# kl26z.net
KiCad netlist of a schematic drawn in EAGLE
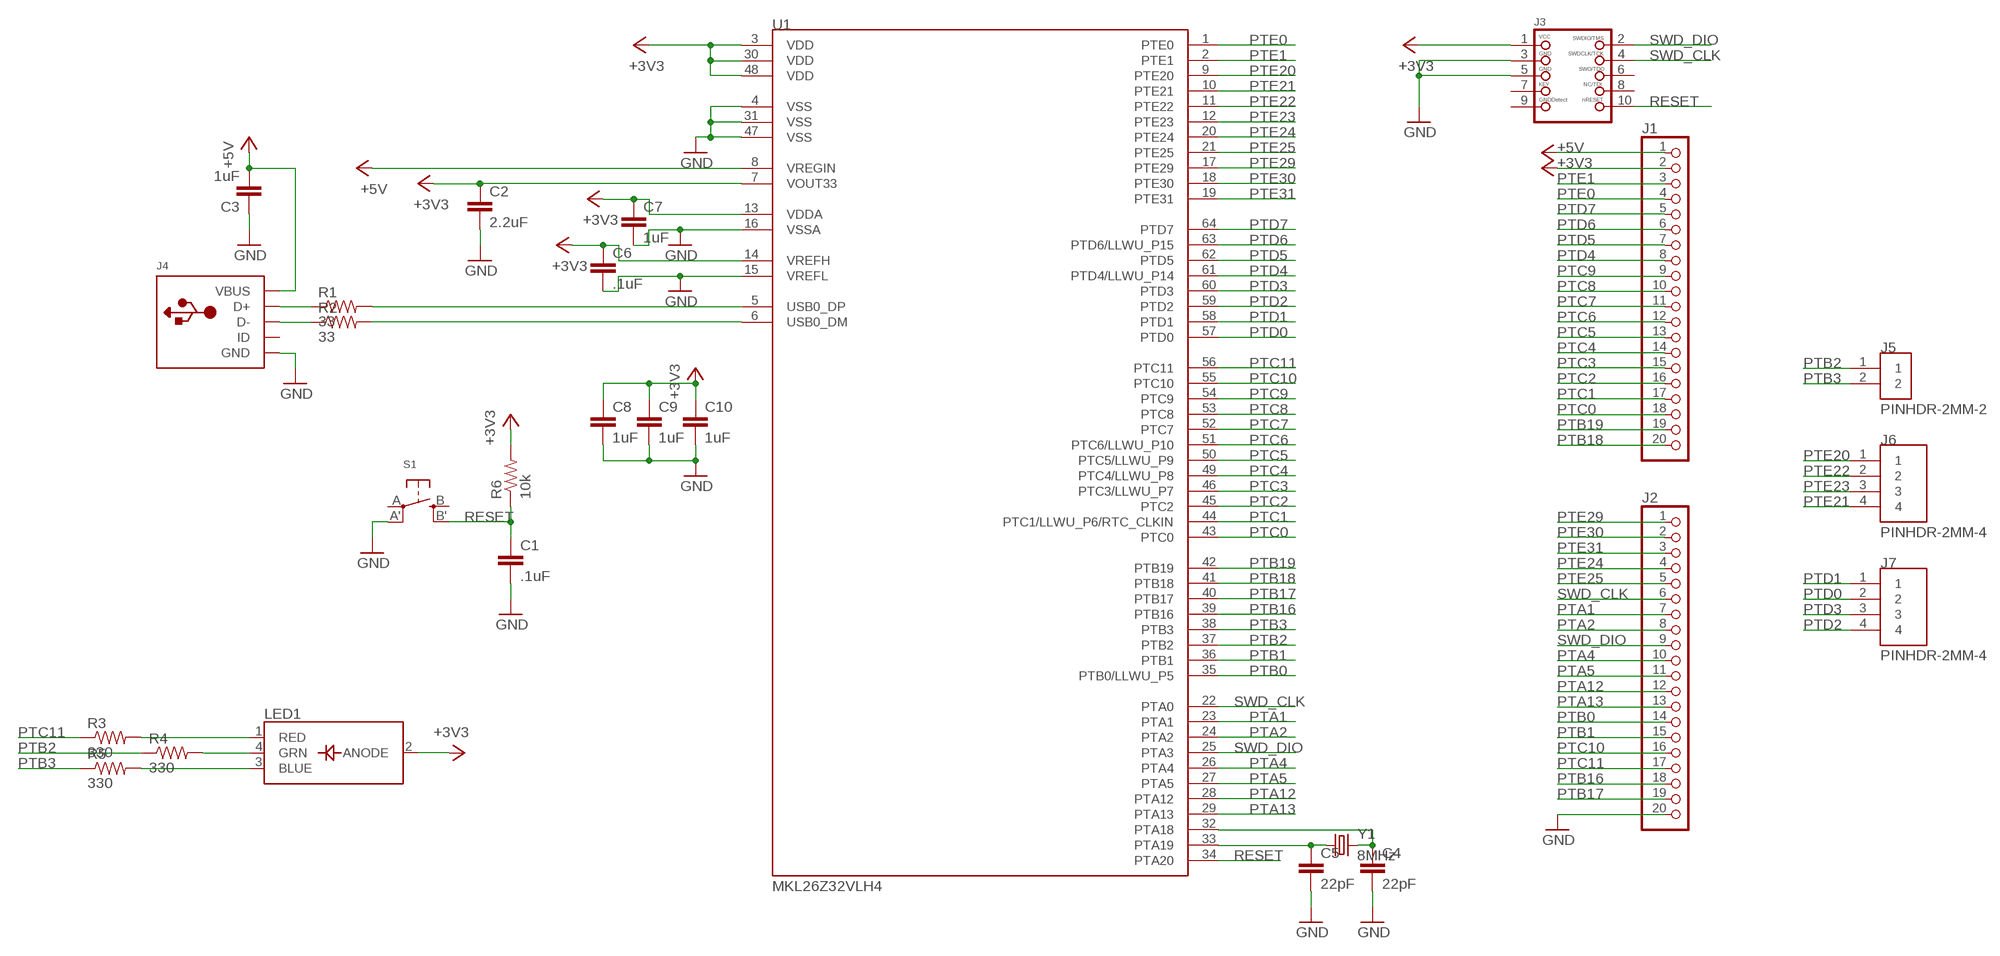
[diagram p0: schematic, sheet 1]

(export (version "E")
  (design (tool "Eeschema 10.0.6"))
  (components
    (comp (ref "C1")
      (value ".1uF")
      (footprint "eagle-import:C0603")
      (libsource (lib "eagle-import") (part "C-EUC0603"))
    )
    (comp (ref "C2")
      (value "2.2uF")
      (footprint "eagle-import:C0603")
      (libsource (lib "eagle-import") (part "C-EUC0603"))
    )
    (comp (ref "C3")
      (value "1uF")
      (footprint "eagle-import:C0603")
      (libsource (lib "eagle-import") (part "C-EUC0603"))
    )
    (comp (ref "C4")
      (value "22pF")
      (footprint "eagle-import:C0603")
      (libsource (lib "eagle-import") (part "C-EUC0603"))
    )
    (comp (ref "C5")
      (value "22pF")
      (footprint "eagle-import:C0603")
      (libsource (lib "eagle-import") (part "C-EUC0603"))
    )
    (comp (ref "C6")
      (value ".1uF")
      (footprint "eagle-import:C0603")
      (libsource (lib "eagle-import") (part "C-EUC0603"))
    )
    (comp (ref "C7")
      (value "1uF")
      (footprint "eagle-import:C0603")
      (libsource (lib "eagle-import") (part "C-EUC0603"))
    )
    (comp (ref "C8")
      (value "1uF")
      (footprint "eagle-import:C0603")
      (libsource (lib "eagle-import") (part "C-EUC0603"))
    )
    (comp (ref "C9")
      (value "1uF")
      (footprint "eagle-import:C0603")
      (libsource (lib "eagle-import") (part "C-EUC0603"))
    )
    (comp (ref "C10")
      (value "1uF")
      (footprint "eagle-import:C0603")
      (libsource (lib "eagle-import") (part "C-EUC0603"))
    )
    (comp (ref "J1")
      (value "HEADER-1X20ROUND")
      (footprint "eagle-import:1X20_ROUND")
      (libsource (lib "eagle-import") (part "HEADER-1X20ROUND"))
    )
    (comp (ref "J2")
      (value "HEADER-1X20ROUND")
      (footprint "eagle-import:1X20_ROUND")
      (libsource (lib "eagle-import") (part "HEADER-1X20ROUND"))
    )
    (comp (ref "J3")
      (value "JTAG-CORTEXM3")
      (footprint "eagle-import:2X05_1.27MM_SMT")
      (libsource (lib "eagle-import") (part "JTAG-CORTEXM3"))
    )
    (comp (ref "J4")
      (value "USBMINIB")
      (footprint "eagle-import:USB-MINIB")
      (libsource (lib "eagle-import") (part "USBMINIB"))
    )
    (comp (ref "J5")
      (value "PINHDR-2MM-2")
      (footprint "eagle-import:PINHDR-2MM-2")
      (libsource (lib "eagle-import") (part "PINHDR-2MM-2"))
    )
    (comp (ref "J6")
      (value "PINHDR-2MM-4")
      (footprint "eagle-import:PINHDR-2MM-4")
      (libsource (lib "eagle-import") (part "PINHDR-2MM-4"))
    )
    (comp (ref "J7")
      (value "PINHDR-2MM-4")
      (footprint "eagle-import:PINHDR-2MM-4")
      (libsource (lib "eagle-import") (part "PINHDR-2MM-4"))
    )
    (comp (ref "LED1")
      (value "LED_RGB_PLCC4")
      (footprint "eagle-import:RGBLED_PLCC4")
      (libsource (lib "eagle-import") (part "LED_RGB_PLCC4"))
    )
    (comp (ref "R1")
      (value "33")
      (footprint "eagle-import:R0603")
      (libsource (lib "eagle-import") (part "R-US_R0603"))
    )
    (comp (ref "R2")
      (value "33")
      (footprint "eagle-import:R0603")
      (libsource (lib "eagle-import") (part "R-US_R0603"))
    )
    (comp (ref "R3")
      (value "330")
      (footprint "eagle-import:R0603")
      (libsource (lib "eagle-import") (part "R-US_R0603"))
    )
    (comp (ref "R4")
      (value "330")
      (footprint "eagle-import:R0603")
      (libsource (lib "eagle-import") (part "R-US_R0603"))
    )
    (comp (ref "R5")
      (value "330")
      (footprint "eagle-import:R0603")
      (libsource (lib "eagle-import") (part "R-US_R0603"))
    )
    (comp (ref "R6")
      (value "10k")
      (footprint "eagle-import:R0603")
      (libsource (lib "eagle-import") (part "R-US_R0603"))
    )
    (comp (ref "S1")
      (value "SWITCH_TACT_SMT4.6X2.8")
      (footprint "eagle-import:BTN_KMR2_4.6X2.8")
      (libsource (lib "eagle-import") (part "SWITCH_TACT_SMT4.6X2.8"))
    )
    (comp (ref "U1")
      (value "MKL26Z32VLH4")
      (footprint "eagle-import:LFQP64")
      (libsource (lib "eagle-import") (part "MKL26Z32VLH4"))
    )
    (comp (ref "Y1")
      (value "8MHz")
      (footprint "eagle-import:CTS406")
      (libsource (lib "eagle-import") (part "CRYSTALCTS406"))
    )
  )
  (nets
    (net (code "1") (name "+3V3") (class "Default")
      (node (ref "C10") (pin "1") (pinfunction "1_1") (pintype "passive"))
      (node (ref "C2") (pin "1") (pinfunction "1_1") (pintype "passive"))
      (node (ref "C6") (pin "1") (pinfunction "1_1") (pintype "passive"))
      (node (ref "C7") (pin "1") (pinfunction "1_1") (pintype "passive"))
      (node (ref "C8") (pin "1") (pinfunction "1_1") (pintype "passive"))
      (node (ref "C9") (pin "1") (pinfunction "1_1") (pintype "passive"))
      (node (ref "J1") (pin "2") (pinfunction "2_2") (pintype "passive"))
      (node (ref "J3") (pin "1") (pinfunction "1_1") (pintype "passive"))
      (node (ref "LED1") (pin "2") (pinfunction "ANODE_2") (pintype "power_in"))
      (node (ref "R6") (pin "2") (pinfunction "2_2") (pintype "passive"))
      (node (ref "U1") (pin "13") (pinfunction "VDDA_13") (pintype "bidirectional"))
      (node (ref "U1") (pin "14") (pinfunction "VREFH_14") (pintype "bidirectional"))
      (node (ref "U1") (pin "3") (pinfunction "VDD_3") (pintype "bidirectional"))
      (node (ref "U1") (pin "30") (pinfunction "VDD_30") (pintype "bidirectional"))
      (node (ref "U1") (pin "48") (pinfunction "VDD_48") (pintype "bidirectional"))
      (node (ref "U1") (pin "7") (pinfunction "VOUT33_7") (pintype "bidirectional"))
    )
    (net (code "2") (name "+5V") (class "Default")
      (node (ref "C3") (pin "2") (pinfunction "2_2") (pintype "passive"))
      (node (ref "J1") (pin "1") (pinfunction "1_1") (pintype "passive"))
      (node (ref "J4") (pin "VBUS") (pinfunction "VBUS_VBUS") (pintype "power_in"))
      (node (ref "U1") (pin "8") (pinfunction "VREGIN_8") (pintype "bidirectional"))
    )
    (net (code "3") (name "/PTA1") (class "Default")
      (node (ref "J2") (pin "7") (pinfunction "7_7") (pintype "passive"))
      (node (ref "U1") (pin "23") (pinfunction "PTA1_23") (pintype "bidirectional"))
    )
    (net (code "4") (name "/PTA2") (class "Default")
      (node (ref "J2") (pin "8") (pinfunction "8_8") (pintype "passive"))
      (node (ref "U1") (pin "24") (pinfunction "PTA2_24") (pintype "bidirectional"))
    )
    (net (code "5") (name "/PTA4") (class "Default")
      (node (ref "J2") (pin "10") (pinfunction "10_10") (pintype "passive"))
      (node (ref "U1") (pin "26") (pinfunction "PTA4_26") (pintype "bidirectional"))
    )
    (net (code "6") (name "/PTA5") (class "Default")
      (node (ref "J2") (pin "11") (pinfunction "11_11") (pintype "passive"))
      (node (ref "U1") (pin "27") (pinfunction "PTA5_27") (pintype "bidirectional"))
    )
    (net (code "7") (name "/PTA12") (class "Default")
      (node (ref "J2") (pin "12") (pinfunction "12_12") (pintype "passive"))
      (node (ref "U1") (pin "28") (pinfunction "PTA12_28") (pintype "bidirectional"))
    )
    (net (code "8") (name "/PTA13") (class "Default")
      (node (ref "J2") (pin "13") (pinfunction "13_13") (pintype "passive"))
      (node (ref "U1") (pin "29") (pinfunction "PTA13_29") (pintype "bidirectional"))
    )
    (net (code "9") (name "/PTB0") (class "Default")
      (node (ref "J2") (pin "14") (pinfunction "14_14") (pintype "passive"))
      (node (ref "U1") (pin "35") (pinfunction "PTB0/LLWU_P5_35") (pintype "bidirectional"))
    )
    (net (code "10") (name "/PTB1") (class "Default")
      (node (ref "J2") (pin "15") (pinfunction "15_15") (pintype "passive"))
      (node (ref "U1") (pin "36") (pinfunction "PTB1_36") (pintype "bidirectional"))
    )
    (net (code "11") (name "/PTB2") (class "Default")
      (node (ref "J5") (pin "1") (pinfunction "1_1") (pintype "bidirectional"))
      (node (ref "R4") (pin "1") (pinfunction "1_1") (pintype "passive"))
      (node (ref "U1") (pin "37") (pinfunction "PTB2_37") (pintype "bidirectional"))
    )
    (net (code "12") (name "/PTB3") (class "Default")
      (node (ref "J5") (pin "2") (pinfunction "2_2") (pintype "bidirectional"))
      (node (ref "R5") (pin "1") (pinfunction "1_1") (pintype "passive"))
      (node (ref "U1") (pin "38") (pinfunction "PTB3_38") (pintype "bidirectional"))
    )
    (net (code "13") (name "/PTB16") (class "Default")
      (node (ref "J2") (pin "18") (pinfunction "18_18") (pintype "passive"))
      (node (ref "U1") (pin "39") (pinfunction "PTB16_39") (pintype "bidirectional"))
    )
    (net (code "14") (name "/PTB17") (class "Default")
      (node (ref "J2") (pin "19") (pinfunction "19_19") (pintype "passive"))
      (node (ref "U1") (pin "40") (pinfunction "PTB17_40") (pintype "bidirectional"))
    )
    (net (code "15") (name "/PTB18") (class "Default")
      (node (ref "J1") (pin "20") (pinfunction "20_20") (pintype "passive"))
      (node (ref "U1") (pin "41") (pinfunction "PTB18_41") (pintype "bidirectional"))
    )
    (net (code "16") (name "/PTB19") (class "Default")
      (node (ref "J1") (pin "19") (pinfunction "19_19") (pintype "passive"))
      (node (ref "U1") (pin "42") (pinfunction "PTB19_42") (pintype "bidirectional"))
    )
    (net (code "17") (name "/PTC0") (class "Default")
      (node (ref "J1") (pin "18") (pinfunction "18_18") (pintype "passive"))
      (node (ref "U1") (pin "43") (pinfunction "PTC0_43") (pintype "bidirectional"))
    )
    (net (code "18") (name "/PTC1") (class "Default")
      (node (ref "J1") (pin "17") (pinfunction "17_17") (pintype "passive"))
      (node (ref "U1") (pin "44") (pinfunction "PTC1/LLWU_P6/RTC_CLKIN_44") (pintype "bidirectional"))
    )
    (net (code "19") (name "/PTC2") (class "Default")
      (node (ref "J1") (pin "16") (pinfunction "16_16") (pintype "passive"))
      (node (ref "U1") (pin "45") (pinfunction "PTC2_45") (pintype "bidirectional"))
    )
    (net (code "20") (name "/PTC3") (class "Default")
      (node (ref "J1") (pin "15") (pinfunction "15_15") (pintype "passive"))
      (node (ref "U1") (pin "46") (pinfunction "PTC3/LLWU_P7_46") (pintype "bidirectional"))
    )
    (net (code "21") (name "/PTC4") (class "Default")
      (node (ref "J1") (pin "14") (pinfunction "14_14") (pintype "passive"))
      (node (ref "U1") (pin "49") (pinfunction "PTC4/LLWU_P8_49") (pintype "bidirectional"))
    )
    (net (code "22") (name "/PTC5") (class "Default")
      (node (ref "J1") (pin "13") (pinfunction "13_13") (pintype "passive"))
      (node (ref "U1") (pin "50") (pinfunction "PTC5/LLWU_P9_50") (pintype "bidirectional"))
    )
    (net (code "23") (name "/PTC6") (class "Default")
      (node (ref "J1") (pin "12") (pinfunction "12_12") (pintype "passive"))
      (node (ref "U1") (pin "51") (pinfunction "PTC6/LLWU_P10_51") (pintype "bidirectional"))
    )
    (net (code "24") (name "/PTC7") (class "Default")
      (node (ref "J1") (pin "11") (pinfunction "11_11") (pintype "passive"))
      (node (ref "U1") (pin "52") (pinfunction "PTC7_52") (pintype "bidirectional"))
    )
    (net (code "25") (name "/PTC8") (class "Default")
      (node (ref "J1") (pin "10") (pinfunction "10_10") (pintype "passive"))
      (node (ref "U1") (pin "53") (pinfunction "PTC8_53") (pintype "bidirectional"))
    )
    (net (code "26") (name "/PTC9") (class "Default")
      (node (ref "J1") (pin "9") (pinfunction "9_9") (pintype "passive"))
      (node (ref "U1") (pin "54") (pinfunction "PTC9_54") (pintype "bidirectional"))
    )
    (net (code "27") (name "/PTC10") (class "Default")
      (node (ref "J2") (pin "16") (pinfunction "16_16") (pintype "passive"))
      (node (ref "U1") (pin "55") (pinfunction "PTC10_55") (pintype "bidirectional"))
    )
    (net (code "28") (name "/PTC11") (class "Default")
      (node (ref "J2") (pin "17") (pinfunction "17_17") (pintype "passive"))
      (node (ref "R3") (pin "1") (pinfunction "1_1") (pintype "passive"))
      (node (ref "U1") (pin "56") (pinfunction "PTC11_56") (pintype "bidirectional"))
    )
    (net (code "29") (name "/PTD0") (class "Default")
      (node (ref "J7") (pin "2") (pinfunction "2_2") (pintype "bidirectional"))
      (node (ref "U1") (pin "57") (pinfunction "PTD0_57") (pintype "bidirectional"))
    )
    (net (code "30") (name "/PTD1") (class "Default")
      (node (ref "J7") (pin "1") (pinfunction "1_1") (pintype "bidirectional"))
      (node (ref "U1") (pin "58") (pinfunction "PTD1_58") (pintype "bidirectional"))
    )
    (net (code "31") (name "/PTD2") (class "Default")
      (node (ref "J7") (pin "4") (pinfunction "4_4") (pintype "bidirectional"))
      (node (ref "U1") (pin "59") (pinfunction "PTD2_59") (pintype "bidirectional"))
    )
    (net (code "32") (name "/PTD3") (class "Default")
      (node (ref "J7") (pin "3") (pinfunction "3_3") (pintype "bidirectional"))
      (node (ref "U1") (pin "60") (pinfunction "PTD3_60") (pintype "bidirectional"))
    )
    (net (code "33") (name "/PTD4") (class "Default")
      (node (ref "J1") (pin "8") (pinfunction "8_8") (pintype "passive"))
      (node (ref "U1") (pin "61") (pinfunction "PTD4/LLWU_P14_61") (pintype "bidirectional"))
    )
    (net (code "34") (name "/PTD5") (class "Default")
      (node (ref "J1") (pin "7") (pinfunction "7_7") (pintype "passive"))
      (node (ref "U1") (pin "62") (pinfunction "PTD5_62") (pintype "bidirectional"))
    )
    (net (code "35") (name "/PTD6") (class "Default")
      (node (ref "J1") (pin "6") (pinfunction "6_6") (pintype "passive"))
      (node (ref "U1") (pin "63") (pinfunction "PTD6/LLWU_P15_63") (pintype "bidirectional"))
    )
    (net (code "36") (name "/PTD7") (class "Default")
      (node (ref "J1") (pin "5") (pinfunction "5_5") (pintype "passive"))
      (node (ref "U1") (pin "64") (pinfunction "PTD7_64") (pintype "bidirectional"))
    )
    (net (code "37") (name "/PTE0") (class "Default")
      (node (ref "J1") (pin "4") (pinfunction "4_4") (pintype "passive"))
      (node (ref "U1") (pin "1") (pinfunction "PTE0_1") (pintype "bidirectional"))
    )
    (net (code "38") (name "/PTE1") (class "Default")
      (node (ref "J1") (pin "3") (pinfunction "3_3") (pintype "passive"))
      (node (ref "U1") (pin "2") (pinfunction "PTE1_2") (pintype "bidirectional"))
    )
    (net (code "39") (name "/PTE20") (class "Default")
      (node (ref "J6") (pin "1") (pinfunction "1_1") (pintype "bidirectional"))
      (node (ref "U1") (pin "9") (pinfunction "PTE20_9") (pintype "bidirectional"))
    )
    (net (code "40") (name "/PTE21") (class "Default")
      (node (ref "J6") (pin "4") (pinfunction "4_4") (pintype "bidirectional"))
      (node (ref "U1") (pin "10") (pinfunction "PTE21_10") (pintype "bidirectional"))
    )
    (net (code "41") (name "/PTE22") (class "Default")
      (node (ref "J6") (pin "2") (pinfunction "2_2") (pintype "bidirectional"))
      (node (ref "U1") (pin "11") (pinfunction "PTE22_11") (pintype "bidirectional"))
    )
    (net (code "42") (name "/PTE23") (class "Default")
      (node (ref "J6") (pin "3") (pinfunction "3_3") (pintype "bidirectional"))
      (node (ref "U1") (pin "12") (pinfunction "PTE23_12") (pintype "bidirectional"))
    )
    (net (code "43") (name "/PTE24") (class "Default")
      (node (ref "J2") (pin "4") (pinfunction "4_4") (pintype "passive"))
      (node (ref "U1") (pin "20") (pinfunction "PTE24_20") (pintype "bidirectional"))
    )
    (net (code "44") (name "/PTE25") (class "Default")
      (node (ref "J2") (pin "5") (pinfunction "5_5") (pintype "passive"))
      (node (ref "U1") (pin "21") (pinfunction "PTE25_21") (pintype "bidirectional"))
    )
    (net (code "45") (name "/PTE29") (class "Default")
      (node (ref "J2") (pin "1") (pinfunction "1_1") (pintype "passive"))
      (node (ref "U1") (pin "17") (pinfunction "PTE29_17") (pintype "bidirectional"))
    )
    (net (code "46") (name "/PTE30") (class "Default")
      (node (ref "J2") (pin "2") (pinfunction "2_2") (pintype "passive"))
      (node (ref "U1") (pin "18") (pinfunction "PTE30_18") (pintype "bidirectional"))
    )
    (net (code "47") (name "/PTE31") (class "Default")
      (node (ref "J2") (pin "3") (pinfunction "3_3") (pintype "passive"))
      (node (ref "U1") (pin "19") (pinfunction "PTE31_19") (pintype "bidirectional"))
    )
    (net (code "48") (name "/RESET") (class "Default")
      (node (ref "C1") (pin "1") (pinfunction "1_1") (pintype "passive"))
      (node (ref "J3") (pin "10") (pinfunction "10_10") (pintype "passive"))
      (node (ref "R6") (pin "1") (pinfunction "1_1") (pintype "passive"))
      (node (ref "S1") (pin "B'") (pinfunction "S1_B'") (pintype "passive"))
      (node (ref "U1") (pin "34") (pinfunction "PTA20_34") (pintype "bidirectional"))
    )
    (net (code "49") (name "/SWD_CLK") (class "Default")
      (node (ref "J2") (pin "6") (pinfunction "6_6") (pintype "passive"))
      (node (ref "J3") (pin "4") (pinfunction "4_4") (pintype "passive"))
      (node (ref "U1") (pin "22") (pinfunction "PTA0_22") (pintype "bidirectional"))
    )
    (net (code "50") (name "/SWD_DIO") (class "Default")
      (node (ref "J2") (pin "9") (pinfunction "9_9") (pintype "passive"))
      (node (ref "J3") (pin "2") (pinfunction "2_2") (pintype "passive"))
      (node (ref "U1") (pin "25") (pinfunction "PTA3_25") (pintype "bidirectional"))
    )
    (net (code "51") (name "GND") (class "Default")
      (node (ref "C1") (pin "2") (pinfunction "2_2") (pintype "passive"))
      (node (ref "C10") (pin "2") (pinfunction "2_2") (pintype "passive"))
      (node (ref "C2") (pin "2") (pinfunction "2_2") (pintype "passive"))
      (node (ref "C3") (pin "1") (pinfunction "1_1") (pintype "passive"))
      (node (ref "C4") (pin "2") (pinfunction "2_2") (pintype "passive"))
      (node (ref "C5") (pin "2") (pinfunction "2_2") (pintype "passive"))
      (node (ref "C6") (pin "2") (pinfunction "2_2") (pintype "passive"))
      (node (ref "C7") (pin "2") (pinfunction "2_2") (pintype "passive"))
      (node (ref "C8") (pin "2") (pinfunction "2_2") (pintype "passive"))
      (node (ref "C9") (pin "2") (pinfunction "2_2") (pintype "passive"))
      (node (ref "J2") (pin "20") (pinfunction "20_20") (pintype "passive"))
      (node (ref "J3") (pin "3") (pinfunction "3_3") (pintype "passive"))
      (node (ref "J3") (pin "5") (pinfunction "5_5") (pintype "passive"))
      (node (ref "J4") (pin "GND") (pinfunction "GND_GND") (pintype "power_in"))
      (node (ref "S1") (pin "A'") (pinfunction "P1_A'") (pintype "passive"))
      (node (ref "U1") (pin "15") (pinfunction "VREFL_15") (pintype "bidirectional"))
      (node (ref "U1") (pin "16") (pinfunction "VSSA_16") (pintype "bidirectional"))
      (node (ref "U1") (pin "31") (pinfunction "VSS_31") (pintype "bidirectional"))
      (node (ref "U1") (pin "4") (pinfunction "VSS_4") (pintype "bidirectional"))
      (node (ref "U1") (pin "47") (pinfunction "VSS_47") (pintype "bidirectional"))
    )
    (net (code "52") (name "Net-(J4-PadD+)") (class "Default")
      (node (ref "J4") (pin "D+") (pinfunction "D+_D+") (pintype "bidirectional"))
      (node (ref "R1") (pin "1") (pinfunction "1_1") (pintype "passive"))
    )
    (net (code "53") (name "Net-(J4-PadD-)") (class "Default")
      (node (ref "J4") (pin "D-") (pinfunction "D-_D-") (pintype "bidirectional"))
      (node (ref "R2") (pin "1") (pinfunction "1_1") (pintype "passive"))
    )
    (net (code "54") (name "Net-(LED1-BLUE)") (class "Default")
      (node (ref "LED1") (pin "3") (pinfunction "BLUE_3") (pintype "bidirectional"))
      (node (ref "R5") (pin "2") (pinfunction "2_2") (pintype "passive"))
    )
    (net (code "55") (name "Net-(LED1-GRN)") (class "Default")
      (node (ref "LED1") (pin "4") (pinfunction "GRN_4") (pintype "bidirectional"))
      (node (ref "R4") (pin "2") (pinfunction "2_2") (pintype "passive"))
    )
    (net (code "56") (name "Net-(LED1-RED)") (class "Default")
      (node (ref "LED1") (pin "1") (pinfunction "RED_1") (pintype "bidirectional"))
      (node (ref "R3") (pin "2") (pinfunction "2_2") (pintype "passive"))
    )
    (net (code "57") (name "Net-(U1-PTA18)") (class "Default")
      (node (ref "C4") (pin "1") (pinfunction "1_1") (pintype "passive"))
      (node (ref "U1") (pin "32") (pinfunction "PTA18_32") (pintype "bidirectional"))
      (node (ref "Y1") (pin "3") (pinfunction "2_3") (pintype "passive"))
    )
    (net (code "58") (name "Net-(U1-PTA19)") (class "Default")
      (node (ref "C5") (pin "1") (pinfunction "1_1") (pintype "passive"))
      (node (ref "U1") (pin "33") (pinfunction "PTA19_33") (pintype "bidirectional"))
      (node (ref "Y1") (pin "1") (pinfunction "1_1") (pintype "passive"))
    )
    (net (code "59") (name "Net-(U1-USB0_DM)") (class "Default")
      (node (ref "R2") (pin "2") (pinfunction "2_2") (pintype "passive"))
      (node (ref "U1") (pin "6") (pinfunction "USB0_DM_6") (pintype "bidirectional"))
    )
    (net (code "60") (name "Net-(U1-USB0_DP)") (class "Default")
      (node (ref "R1") (pin "2") (pinfunction "2_2") (pintype "passive"))
      (node (ref "U1") (pin "5") (pinfunction "USB0_DP_5") (pintype "bidirectional"))
    )
    (net (code "61") (name "unconnected-(J3-Pad6)") (class "Default")
      (node (ref "J3") (pin "6") (pinfunction "6_6") (pintype "passive"))
    )
    (net (code "62") (name "unconnected-(J3-Pad7)") (class "Default")
      (node (ref "J3") (pin "7") (pinfunction "7_7") (pintype "passive"))
    )
    (net (code "63") (name "unconnected-(J3-Pad8)") (class "Default")
      (node (ref "J3") (pin "8") (pinfunction "8_8") (pintype "passive"))
    )
    (net (code "64") (name "unconnected-(J3-Pad9)") (class "Default")
      (node (ref "J3") (pin "9") (pinfunction "9_9") (pintype "passive"))
    )
    (net (code "65") (name "unconnected-(J4-PadID)") (class "Default")
      (node (ref "J4") (pin "ID") (pinfunction "ID_ID") (pintype "bidirectional"))
    )
    (net (code "66") (name "unconnected-(S1-P-PadA)") (class "Default")
      (node (ref "S1") (pin "A") (pinfunction "P_A") (pintype "passive"))
    )
    (net (code "67") (name "unconnected-(S1-S-PadB)") (class "Default")
      (node (ref "S1") (pin "B") (pinfunction "S_B") (pintype "passive"))
    )
  )
)
